# Accumulator.net
KiCad netlist of a schematic drawn in Altium Designer
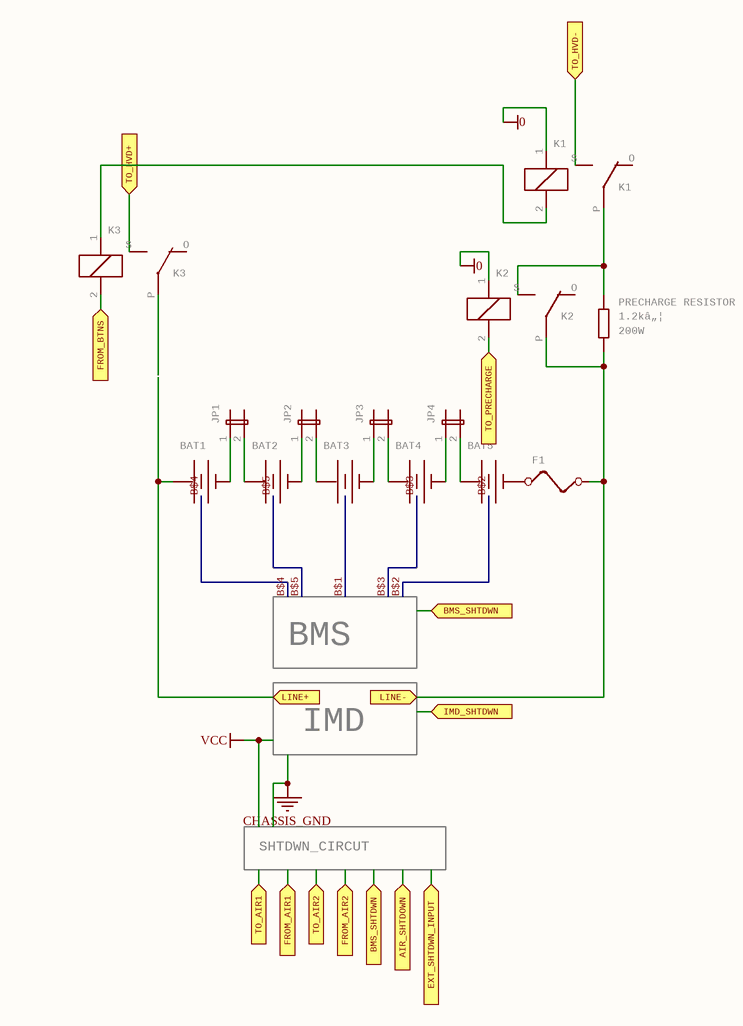
[diagram p0: Accumulator.SchDoc]

(export (version "E")
  (design (tool "Eeschema 10.0.6"))
  (components
    (comp (ref "BAT1") (value "BATTERY") (footprint "BATTERY") (libsource (lib "special") (part "BATTERY")))
    (comp (ref "BAT2") (value "BATTERY") (footprint "BATTERY") (libsource (lib "special") (part "BATTERY")))
    (comp (ref "BAT3") (value "BATTERY") (footprint "BATTERY") (libsource (lib "special") (part "BATTERY")))
    (comp (ref "BAT4") (value "BATTERY") (footprint "BATTERY") (libsource (lib "special") (part "BATTERY")))
    (comp (ref "BAT5") (value "BATTERY") (footprint "BATTERY") (libsource (lib "special") (part "BATTERY")))
    (comp (ref "F1")
      (value "FUSE")
      (footprint "FUSE")
      (description "FUSE   5 x 20 mm")
      (libsource (lib "special") (part "FUSE"))
    )
    (comp (ref "JP1")
      (value "JP1E")
      (footprint "JP1")
      (description "JUMPER")
      (libsource (lib "jumper") (part "JP1E"))
    )
    (comp (ref "JP2")
      (value "JP1E")
      (footprint "JP1")
      (description "JUMPER")
      (libsource (lib "jumper") (part "JP1E"))
    )
    (comp (ref "JP3")
      (value "JP1E")
      (footprint "JP1")
      (description "JUMPER")
      (libsource (lib "jumper") (part "JP1E"))
    )
    (comp (ref "JP4")
      (value "JP1E")
      (footprint "JP1")
      (description "JUMPER")
      (libsource (lib "jumper") (part "JP1E"))
    )
    (comp (ref "K1")
      (value "E3206S")
      (footprint "E3206S")
      (description "RELAY   1 x switch, Eichhoff/distributor Schukat")
      (fields (field (name "PART") "K1") (field (name "MF") "MF") (field (name "MPN") "MPN"))
      (libsource (lib "relay") (part "E3206S"))
    )
    (comp (ref "K2")
      (value "E3206S")
      (footprint "E3206S")
      (description "RELAY   1 x switch, Eichhoff/distributor Schukat")
      (fields (field (name "PART") "K2") (field (name "MF") "MF") (field (name "MPN") "MPN"))
      (libsource (lib "relay") (part "E3206S"))
    )
    (comp (ref "K3")
      (value "E3206S")
      (footprint "E3206S")
      (description "RELAY   1 x switch, Eichhoff/distributor Schukat")
      (fields (field (name "PART") "K3") (field (name "MF") "MF") (field (name "MPN") "MPN"))
      (libsource (lib "relay") (part "E3206S"))
    )
    (comp (ref "R1")
      (value "R")
      (description "RESISTOR")
      (fields (field (name "LIBRARYNAME") "docu-dummy"))
      (libsource (lib "docu-dummy") (part "R"))
    )
  )
  (nets
    (net (code "11") (name "/FROM_BTNS") (class "Default")
      (node (ref "K3") (pin "2") (pinfunction "2_2") (pintype "passive"))
    )
    (net (code "13") (name "/LINE+") (class "Default")
      (node (ref "BAT1") (pin "+") (pinfunction "+_+") (pintype "power_in"))
    )
    (net (code "14") (name "/LINE-") (class "Default")
      (node (ref "F1") (pin "2") (pinfunction "2_2") (pintype "passive"))
      (node (ref "K2") (pin "P") (pinfunction "P_P") (pintype "passive"))
    )
    (net (code "17") (name "/TO_HVD+") (class "Default")
      (node (ref "K3") (pin "S") (pinfunction "S_S") (pintype "passive"))
    )
    (net (code "18") (name "/TO_HVD-") (class "Default")
      (node (ref "K1") (pin "S") (pinfunction "S_S") (pintype "passive"))
    )
    (net (code "19") (name "/TO_PRECHARGE") (class "Default")
      (node (ref "K2") (pin "2") (pinfunction "2_2") (pintype "passive"))
    )
    (net (code "25") (name "0") (class "Default")
      (node (ref "K1") (pin "1") (pinfunction "1_1") (pintype "passive"))
      (node (ref "K2") (pin "1") (pinfunction "1_1") (pintype "passive"))
    )
    (net (code "27") (name "Net-(BAT1-Pad-)") (class "Default")
      (node (ref "BAT1") (pin "-") (pinfunction "-_-") (pintype "power_in"))
      (node (ref "JP1") (pin "1") (pinfunction "1_1") (pintype "passive"))
    )
    (net (code "28") (name "Net-(BAT2-Pad+)") (class "Default")
      (node (ref "BAT2") (pin "+") (pinfunction "+_+") (pintype "power_in"))
      (node (ref "JP1") (pin "2") (pinfunction "2_2") (pintype "passive"))
    )
    (net (code "29") (name "Net-(BAT2-Pad-)") (class "Default")
      (node (ref "BAT2") (pin "-") (pinfunction "-_-") (pintype "power_in"))
      (node (ref "JP2") (pin "1") (pinfunction "1_1") (pintype "passive"))
    )
    (net (code "30") (name "Net-(BAT3-Pad+)") (class "Default")
      (node (ref "BAT3") (pin "+") (pinfunction "+_+") (pintype "power_in"))
      (node (ref "JP2") (pin "2") (pinfunction "2_2") (pintype "passive"))
    )
    (net (code "31") (name "Net-(BAT3-Pad-)") (class "Default")
      (node (ref "BAT3") (pin "-") (pinfunction "-_-") (pintype "power_in"))
      (node (ref "JP3") (pin "1") (pinfunction "1_1") (pintype "passive"))
    )
    (net (code "32") (name "Net-(BAT4-Pad+)") (class "Default")
      (node (ref "BAT4") (pin "+") (pinfunction "+_+") (pintype "power_in"))
      (node (ref "JP3") (pin "2") (pinfunction "2_2") (pintype "passive"))
    )
    (net (code "33") (name "Net-(BAT4-Pad-)") (class "Default")
      (node (ref "BAT4") (pin "-") (pinfunction "-_-") (pintype "power_in"))
      (node (ref "JP4") (pin "1") (pinfunction "1_1") (pintype "passive"))
    )
    (net (code "34") (name "Net-(BAT5-Pad+)") (class "Default")
      (node (ref "BAT5") (pin "+") (pinfunction "+_+") (pintype "power_in"))
      (node (ref "JP4") (pin "2") (pinfunction "2_2") (pintype "passive"))
    )
    (net (code "35") (name "Net-(BAT5-Pad-)") (class "Default")
      (node (ref "BAT5") (pin "-") (pinfunction "-_-") (pintype "power_in"))
      (node (ref "F1") (pin "1") (pinfunction "1_1") (pintype "passive"))
    )
    (net (code "36") (name "Net-(K1-Pad2)") (class "Default")
      (node (ref "K1") (pin "2") (pinfunction "2_2") (pintype "passive"))
      (node (ref "K3") (pin "1") (pinfunction "1_1") (pintype "passive"))
    )
    (net (code "37") (name "Net-(K1-PadP)") (class "Default")
      (node (ref "K1") (pin "P") (pinfunction "P_P") (pintype "passive"))
      (node (ref "K2") (pin "S") (pinfunction "S_S") (pintype "passive"))
    )
    (net (code "39") (name "unconnected-(BAT1-+-Pad+@1)") (class "Default")
      (node (ref "BAT1") (pin "+@1") (pinfunction "+_+@1") (pintype "power_in"))
    )
    (net (code "40") (name "unconnected-(BAT2-+-Pad+@1)") (class "Default")
      (node (ref "BAT2") (pin "+@1") (pinfunction "+_+@1") (pintype "power_in"))
    )
    (net (code "41") (name "unconnected-(BAT3-+-Pad+@1)") (class "Default")
      (node (ref "BAT3") (pin "+@1") (pinfunction "+_+@1") (pintype "power_in"))
    )
    (net (code "42") (name "unconnected-(BAT4-+-Pad+@1)") (class "Default")
      (node (ref "BAT4") (pin "+@1") (pinfunction "+_+@1") (pintype "power_in"))
    )
    (net (code "43") (name "unconnected-(BAT5-+-Pad+@1)") (class "Default")
      (node (ref "BAT5") (pin "+@1") (pinfunction "+_+@1") (pintype "power_in"))
    )
    (net (code "44") (name "unconnected-(K1-PadO)") (class "Default")
      (node (ref "K1") (pin "O") (pinfunction "O_O") (pintype "passive"))
    )
    (net (code "45") (name "unconnected-(K2-PadO)") (class "Default")
      (node (ref "K2") (pin "O") (pinfunction "O_O") (pintype "passive"))
    )
    (net (code "46") (name "unconnected-(K3-PadO)") (class "Default")
      (node (ref "K3") (pin "O") (pinfunction "O_O") (pintype "passive"))
    )
    (net (code "47") (name "unconnected-(K3-PadP)") (class "Default")
      (node (ref "K3") (pin "P") (pinfunction "P_P") (pintype "passive"))
    )
  )
)
